# Wiegand_RF.net
KiCad netlist of a schematic drawn in EAGLE
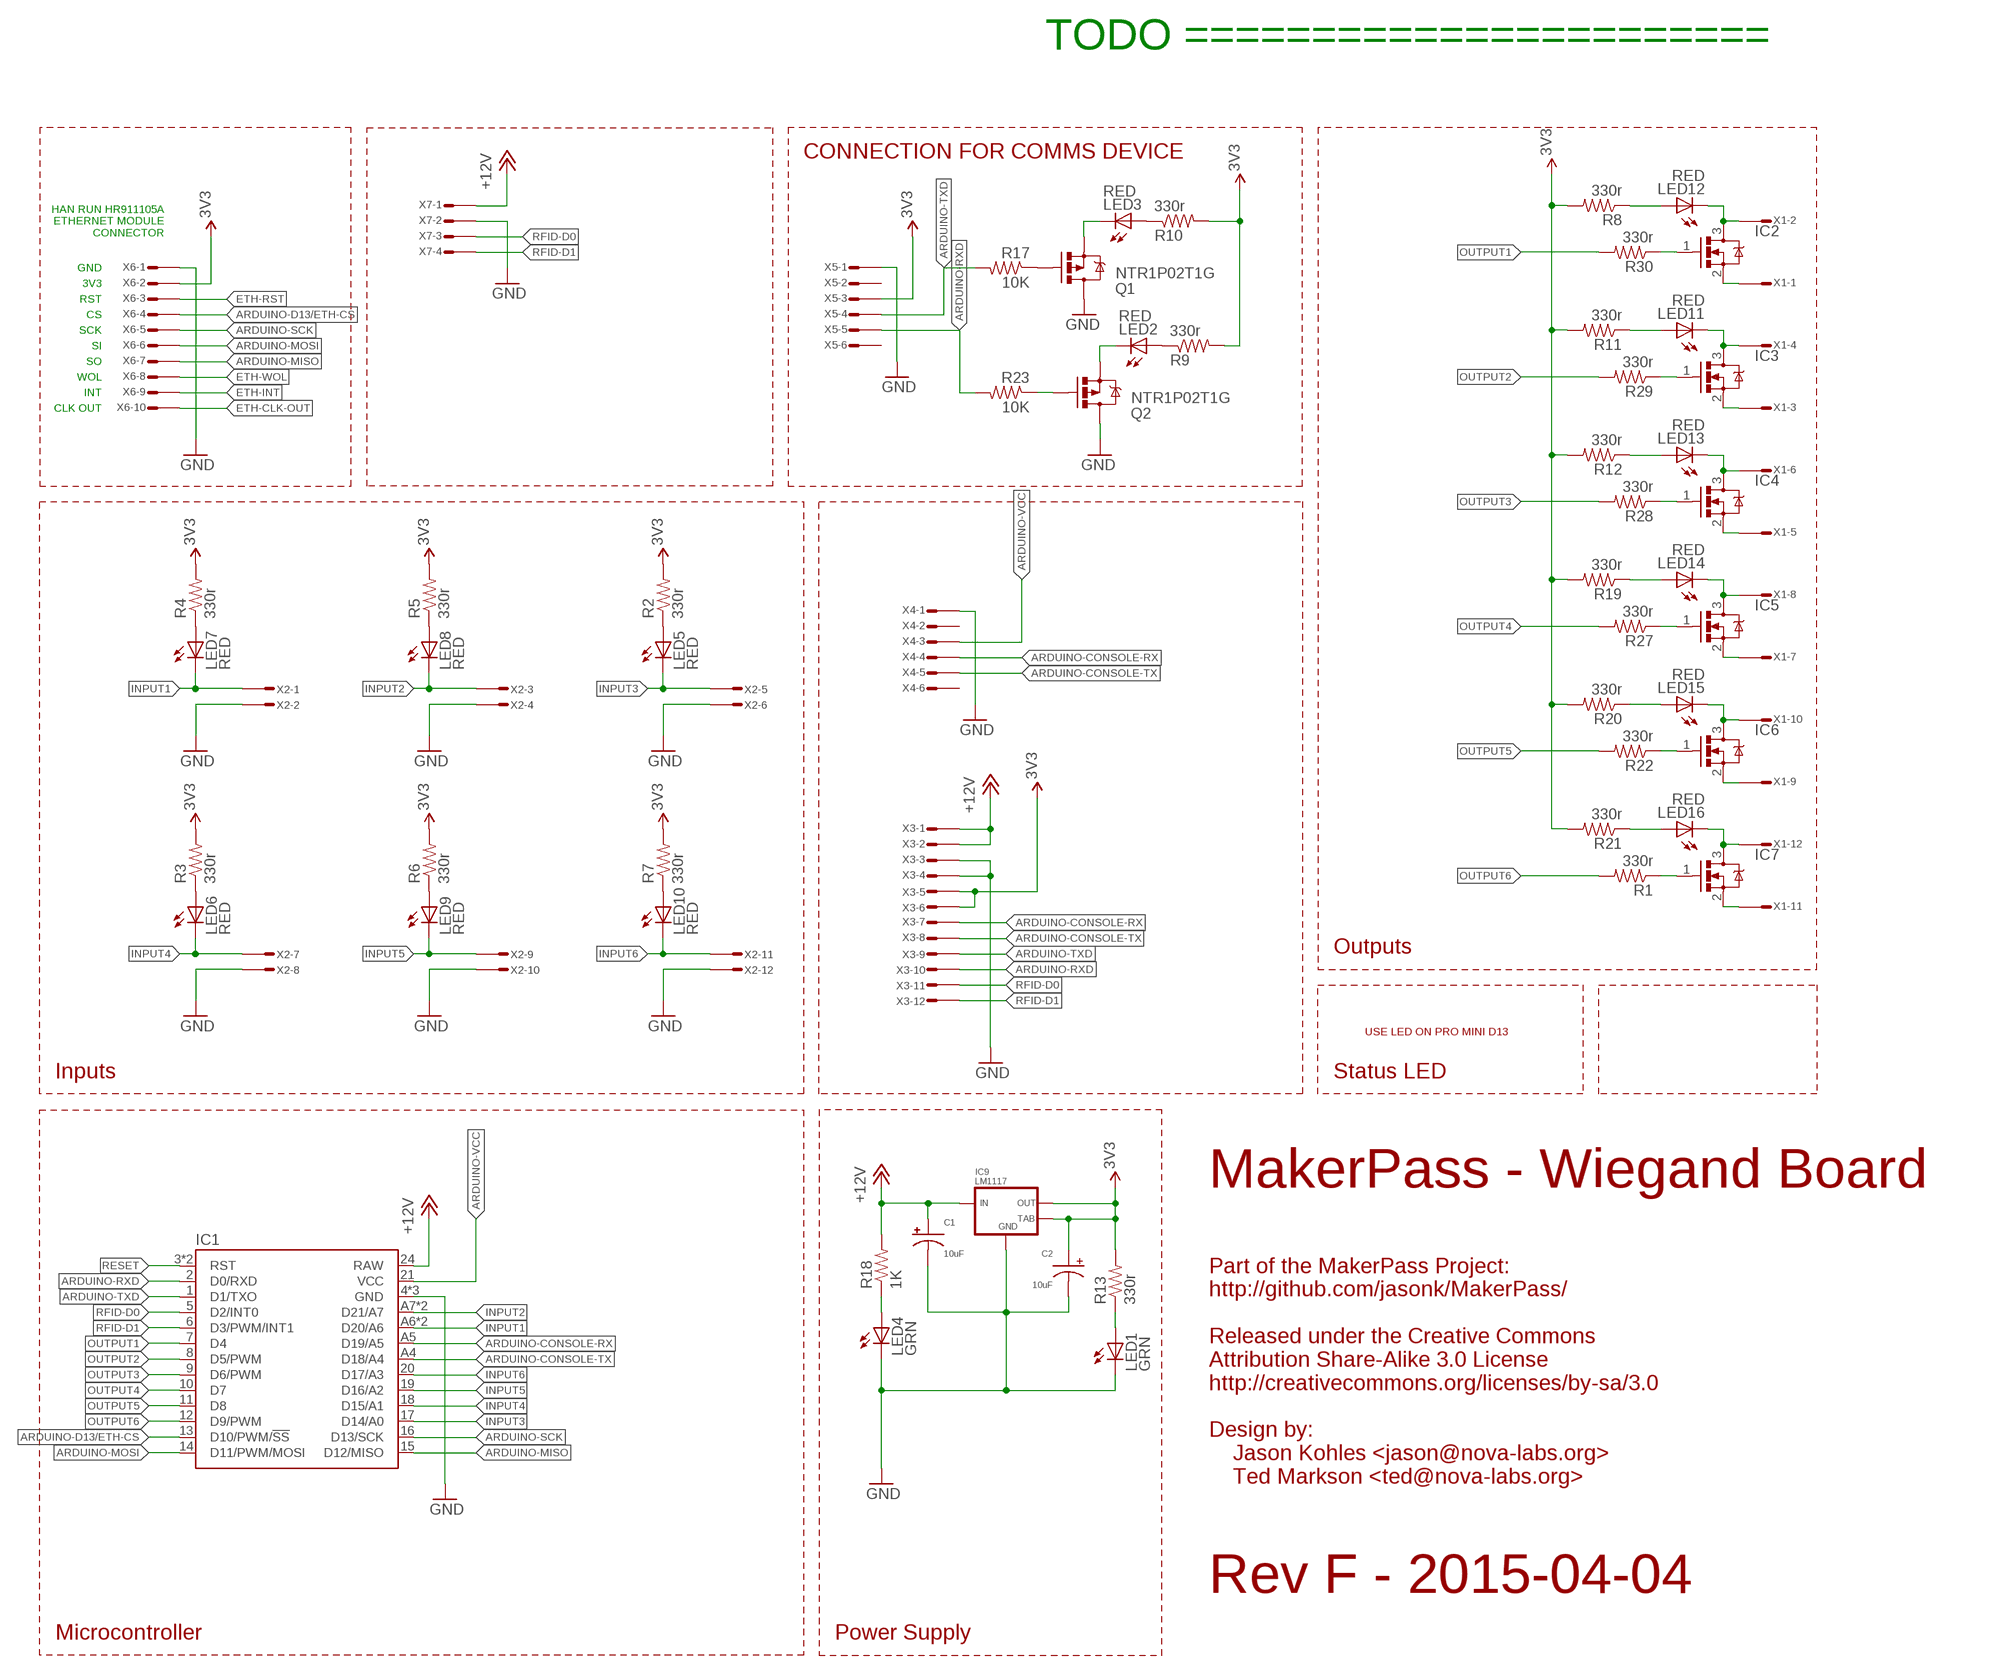
[diagram p0: schematic, sheet 1]

(export (version "E")
  (design (tool "Eeschema 10.0.6"))
  (components
    (comp (ref "C1")
      (value "10uF")
      (footprint "eagle-import:C-CAN-4.3")
      (fields
        (field (name "MFG") "UNITED CHEMI-CON")
        (field (name "MFG_PN") "EMVA250ADA100MD55G")
        (field (name "SUPP") "DIGIKEY")
        (field (name "SUPP_PN") "565-2100-1-ND")
      )
      (libsource (lib "eagle-import") (part "C-POL-CAN-4.3"))
    )
    (comp (ref "C2")
      (value "10uF")
      (footprint "eagle-import:C-CAN-4.3")
      (fields
        (field (name "MFG") "UNITED CHEMI-CON")
        (field (name "MFG_PN") "EMVA250ADA100MD55G")
        (field (name "SUPP") "DIGIKEY")
        (field (name "SUPP_PN") "565-2100-1-ND")
      )
      (libsource (lib "eagle-import") (part "C-POL-CAN-4.3"))
    )
    (comp (ref "IC1")
      (value "ARDUINO-PRO-MINI-ALIEXPRESS")
      (footprint "eagle-import:ARDUINO-PRO-MINI-ALIEXPRESS")
      (libsource (lib "eagle-import") (part "ARDUINO-PRO-MINI-ALIEXPRESS"))
    )
    (comp (ref "IC2")
      (value "MOSFET-NCHANNEL-SOT23")
      (footprint "eagle-import:SOT23")
      (fields (field (name "MFG") "DIODES INC"))
      (libsource (lib "eagle-import") (part "MOSFET-NCHANNEL-SOT23"))
    )
    (comp (ref "IC3")
      (value "MOSFET-NCHANNEL-SOT23")
      (footprint "eagle-import:SOT23")
      (fields (field (name "MFG") "DIODES INC"))
      (libsource (lib "eagle-import") (part "MOSFET-NCHANNEL-SOT23"))
    )
    (comp (ref "IC4")
      (value "MOSFET-NCHANNEL-SOT23")
      (footprint "eagle-import:SOT23")
      (fields (field (name "MFG") "DIODES INC"))
      (libsource (lib "eagle-import") (part "MOSFET-NCHANNEL-SOT23"))
    )
    (comp (ref "IC5")
      (value "MOSFET-NCHANNEL-SOT23")
      (footprint "eagle-import:SOT23")
      (fields (field (name "MFG") "DIODES INC"))
      (libsource (lib "eagle-import") (part "MOSFET-NCHANNEL-SOT23"))
    )
    (comp (ref "IC6")
      (value "MOSFET-NCHANNEL-SOT23")
      (footprint "eagle-import:SOT23")
      (fields (field (name "MFG") "DIODES INC"))
      (libsource (lib "eagle-import") (part "MOSFET-NCHANNEL-SOT23"))
    )
    (comp (ref "IC7")
      (value "MOSFET-NCHANNEL-SOT23")
      (footprint "eagle-import:SOT23")
      (fields (field (name "MFG") "DIODES INC"))
      (libsource (lib "eagle-import") (part "MOSFET-NCHANNEL-SOT23"))
    )
    (comp (ref "IC9")
      (value "LM1117")
      (footprint "eagle-import:SOT223")
      (fields
        (field (name "MFG") "TEXAS INSTRUMENTS")
        (field (name "MFG_PN") "LM1117MPX-3.3/NOPB")
        (field (name "SUPP") "DIGIKEY")
        (field (name "SUPP_PN") "LM1117MPX-3.3/NOPBCT-ND")
      )
      (libsource (lib "eagle-import") (part "VREG-LD1117-SOT223"))
    )
    (comp (ref "LED1")
      (value "GRN")
      (footprint "eagle-import:LED-805")
      (libsource (lib "eagle-import") (part "LED-0805"))
    )
    (comp (ref "LED2")
      (value "RED")
      (footprint "eagle-import:LED-805")
      (libsource (lib "eagle-import") (part "LED-0805"))
    )
    (comp (ref "LED3")
      (value "RED")
      (footprint "eagle-import:LED-805")
      (libsource (lib "eagle-import") (part "LED-0805"))
    )
    (comp (ref "LED4")
      (value "GRN")
      (footprint "eagle-import:LED-805")
      (libsource (lib "eagle-import") (part "LED-0805"))
    )
    (comp (ref "LED5")
      (value "RED")
      (footprint "eagle-import:LED-805")
      (libsource (lib "eagle-import") (part "LED-0805"))
    )
    (comp (ref "LED6")
      (value "RED")
      (footprint "eagle-import:LED-805")
      (libsource (lib "eagle-import") (part "LED-0805"))
    )
    (comp (ref "LED7")
      (value "RED")
      (footprint "eagle-import:LED-805")
      (libsource (lib "eagle-import") (part "LED-0805"))
    )
    (comp (ref "LED8")
      (value "RED")
      (footprint "eagle-import:LED-805")
      (libsource (lib "eagle-import") (part "LED-0805"))
    )
    (comp (ref "LED9")
      (value "RED")
      (footprint "eagle-import:LED-805")
      (libsource (lib "eagle-import") (part "LED-0805"))
    )
    (comp (ref "LED10")
      (value "RED")
      (footprint "eagle-import:LED-805")
      (libsource (lib "eagle-import") (part "LED-0805"))
    )
    (comp (ref "LED11")
      (value "RED")
      (footprint "eagle-import:LED-805")
      (libsource (lib "eagle-import") (part "LED-0805"))
    )
    (comp (ref "LED12")
      (value "RED")
      (footprint "eagle-import:LED-805")
      (libsource (lib "eagle-import") (part "LED-0805"))
    )
    (comp (ref "LED13")
      (value "RED")
      (footprint "eagle-import:LED-805")
      (libsource (lib "eagle-import") (part "LED-0805"))
    )
    (comp (ref "LED14")
      (value "RED")
      (footprint "eagle-import:LED-805")
      (libsource (lib "eagle-import") (part "LED-0805"))
    )
    (comp (ref "LED15")
      (value "RED")
      (footprint "eagle-import:LED-805")
      (libsource (lib "eagle-import") (part "LED-0805"))
    )
    (comp (ref "LED16")
      (value "RED")
      (footprint "eagle-import:LED-805")
      (libsource (lib "eagle-import") (part "LED-0805"))
    )
    (comp (ref "Q1")
      (value "NTR1P02T1G")
      (footprint "eagle-import:SOT23-3")
      (libsource (lib "eagle-import") (part "MOSFET-PCHANNELSMD"))
    )
    (comp (ref "Q2")
      (value "NTR1P02T1G")
      (footprint "eagle-import:SOT23-3")
      (libsource (lib "eagle-import") (part "MOSFET-PCHANNELSMD"))
    )
    (comp (ref "R1")
      (value "330r")
      (footprint "eagle-import:0603-RES")
      (libsource (lib "eagle-import") (part "RESISTOR0603-RES"))
    )
    (comp (ref "R2")
      (value "330r")
      (footprint "eagle-import:0603-RES")
      (libsource (lib "eagle-import") (part "RESISTOR0603-RES"))
    )
    (comp (ref "R3")
      (value "330r")
      (footprint "eagle-import:0603-RES")
      (libsource (lib "eagle-import") (part "RESISTOR0603-RES"))
    )
    (comp (ref "R4")
      (value "330r")
      (footprint "eagle-import:0603-RES")
      (libsource (lib "eagle-import") (part "RESISTOR0603-RES"))
    )
    (comp (ref "R5")
      (value "330r")
      (footprint "eagle-import:0603-RES")
      (libsource (lib "eagle-import") (part "RESISTOR0603-RES"))
    )
    (comp (ref "R6")
      (value "330r")
      (footprint "eagle-import:0603-RES")
      (libsource (lib "eagle-import") (part "RESISTOR0603-RES"))
    )
    (comp (ref "R7")
      (value "330r")
      (footprint "eagle-import:0603-RES")
      (libsource (lib "eagle-import") (part "RESISTOR0603-RES"))
    )
    (comp (ref "R8")
      (value "330r")
      (footprint "eagle-import:0603-RES")
      (libsource (lib "eagle-import") (part "RESISTOR0603-RES"))
    )
    (comp (ref "R9")
      (value "330r")
      (footprint "eagle-import:0603-RES")
      (libsource (lib "eagle-import") (part "RESISTOR0603-RES"))
    )
    (comp (ref "R10")
      (value "330r")
      (footprint "eagle-import:0603-RES")
      (libsource (lib "eagle-import") (part "RESISTOR0603-RES"))
    )
    (comp (ref "R11")
      (value "330r")
      (footprint "eagle-import:0603-RES")
      (libsource (lib "eagle-import") (part "RESISTOR0603-RES"))
    )
    (comp (ref "R12")
      (value "330r")
      (footprint "eagle-import:0603-RES")
      (libsource (lib "eagle-import") (part "RESISTOR0603-RES"))
    )
    (comp (ref "R13")
      (value "330r")
      (footprint "eagle-import:0603-RES")
      (libsource (lib "eagle-import") (part "RESISTOR0603-RES"))
    )
    (comp (ref "R17")
      (value "10K")
      (footprint "eagle-import:0603-RES")
      (libsource (lib "eagle-import") (part "RESISTOR0603-RES"))
    )
    (comp (ref "R18")
      (value "1K")
      (footprint "eagle-import:0603-RES")
      (libsource (lib "eagle-import") (part "RESISTOR0603-RES"))
    )
    (comp (ref "R19")
      (value "330r")
      (footprint "eagle-import:0603-RES")
      (libsource (lib "eagle-import") (part "RESISTOR0603-RES"))
    )
    (comp (ref "R20")
      (value "330r")
      (footprint "eagle-import:0603-RES")
      (libsource (lib "eagle-import") (part "RESISTOR0603-RES"))
    )
    (comp (ref "R21")
      (value "330r")
      (footprint "eagle-import:0603-RES")
      (libsource (lib "eagle-import") (part "RESISTOR0603-RES"))
    )
    (comp (ref "R22")
      (value "330r")
      (footprint "eagle-import:0603-RES")
      (libsource (lib "eagle-import") (part "RESISTOR0603-RES"))
    )
    (comp (ref "R23")
      (value "10K")
      (footprint "eagle-import:0603-RES")
      (libsource (lib "eagle-import") (part "RESISTOR0603-RES"))
    )
    (comp (ref "R27")
      (value "330r")
      (footprint "eagle-import:0603-RES")
      (libsource (lib "eagle-import") (part "RESISTOR0603-RES"))
    )
    (comp (ref "R28")
      (value "330r")
      (footprint "eagle-import:0603-RES")
      (libsource (lib "eagle-import") (part "RESISTOR0603-RES"))
    )
    (comp (ref "R29")
      (value "330r")
      (footprint "eagle-import:0603-RES")
      (libsource (lib "eagle-import") (part "RESISTOR0603-RES"))
    )
    (comp (ref "R30")
      (value "330r")
      (footprint "eagle-import:0603-RES")
      (libsource (lib "eagle-import") (part "RESISTOR0603-RES"))
    )
    (comp (ref "X1")
      (value "CON-1X12-TERMBLOCK-3.5MM")
      (footprint "eagle-import:CON-1X12-TERMBLOCK-3.5MM")
      (fields
        (field (name "MFG") "ON SHORE")
        (field (name "MFG_PN") "OSTTE120104")
        (field (name "SUPP") "DIGIKEY")
        (field (name "SUPP_PN") "ED2737-ND")
      )
      (libsource (lib "eagle-import") (part "CON-1X12-TERMBLOCK-3.5MM"))
    )
    (comp (ref "X2")
      (value "CON-1X12-TERMBLOCK-3.5MM")
      (footprint "eagle-import:CON-1X12-TERMBLOCK-3.5MM")
      (fields
        (field (name "MFG") "ON SHORE")
        (field (name "MFG_PN") "OSTTE120104")
        (field (name "SUPP") "DIGIKEY")
        (field (name "SUPP_PN") "ED2737-ND")
      )
      (libsource (lib "eagle-import") (part "CON-1X12-TERMBLOCK-3.5MM"))
    )
    (comp (ref "X3")
      (value "CON-1X12-TERMBLOCK-3.5MM")
      (footprint "eagle-import:CON-1X12-TERMBLOCK-3.5MM")
      (fields
        (field (name "MFG") "ON SHORE")
        (field (name "MFG_PN") "OSTTE120104")
        (field (name "SUPP") "DIGIKEY")
        (field (name "SUPP_PN") "ED2737-ND")
      )
      (libsource (lib "eagle-import") (part "CON-1X12-TERMBLOCK-3.5MM"))
    )
    (comp (ref "X4")
      (value "CON-1X6-FTDI-AVR")
      (footprint "eagle-import:CON-1X6-FTDI-AVR")
      (libsource (lib "eagle-import") (part "CON-1X6-FTDI-AVR"))
    )
    (comp (ref "X5")
      (value "CON-1X6-FTDI-AVR")
      (footprint "eagle-import:CON-1X6-FTDI-AVR")
      (libsource (lib "eagle-import") (part "CON-1X6-FTDI-AVR"))
    )
    (comp (ref "X6")
      (value "CON-2X5")
      (footprint "eagle-import:CON-2X5")
      (libsource (lib "eagle-import") (part "CON-2X5"))
    )
    (comp (ref "X7")
      (value "CON-1X4")
      (footprint "eagle-import:CON-1X4")
      (libsource (lib "eagle-import") (part "CON-1X4"))
    )
  )
  (nets
    (net (code "1") (name "+12V") (class "Default")
      (node (ref "C1") (pin "+") (pinfunction "+_+") (pintype "passive"))
      (node (ref "IC1") (pin "24") (pinfunction "RAW_24") (pintype "power_in"))
      (node (ref "IC9") (pin "IN") (pinfunction "IN_IN") (pintype "power_in"))
      (node (ref "R18") (pin "2") (pinfunction "2_2") (pintype "passive"))
      (node (ref "X3") (pin "1") (pinfunction "S_1") (pintype "passive"))
      (node (ref "X3") (pin "2") (pinfunction "S_2") (pintype "passive"))
      (node (ref "X7") (pin "1") (pinfunction "S_1") (pintype "passive"))
    )
    (net (code "2") (name "3V3") (class "Default")
      (node (ref "C2") (pin "+") (pinfunction "+_+") (pintype "passive"))
      (node (ref "IC9") (pin "OUT") (pinfunction "OUT_OUT") (pintype "power_in"))
      (node (ref "IC9") (pin "TAB") (pinfunction "TAB_TAB") (pintype "power_in"))
      (node (ref "R10") (pin "2") (pinfunction "2_2") (pintype "passive"))
      (node (ref "R11") (pin "2") (pinfunction "2_2") (pintype "passive"))
      (node (ref "R12") (pin "2") (pinfunction "2_2") (pintype "passive"))
      (node (ref "R13") (pin "2") (pinfunction "2_2") (pintype "passive"))
      (node (ref "R19") (pin "2") (pinfunction "2_2") (pintype "passive"))
      (node (ref "R2") (pin "2") (pinfunction "2_2") (pintype "passive"))
      (node (ref "R20") (pin "2") (pinfunction "2_2") (pintype "passive"))
      (node (ref "R21") (pin "2") (pinfunction "2_2") (pintype "passive"))
      (node (ref "R3") (pin "2") (pinfunction "2_2") (pintype "passive"))
      (node (ref "R4") (pin "2") (pinfunction "2_2") (pintype "passive"))
      (node (ref "R5") (pin "2") (pinfunction "2_2") (pintype "passive"))
      (node (ref "R6") (pin "2") (pinfunction "2_2") (pintype "passive"))
      (node (ref "R7") (pin "2") (pinfunction "2_2") (pintype "passive"))
      (node (ref "R8") (pin "2") (pinfunction "2_2") (pintype "passive"))
      (node (ref "R9") (pin "2") (pinfunction "2_2") (pintype "passive"))
      (node (ref "X3") (pin "5") (pinfunction "S_5") (pintype "passive"))
      (node (ref "X3") (pin "6") (pinfunction "S_6") (pintype "passive"))
      (node (ref "X5") (pin "3") (pinfunction "S_3") (pintype "passive"))
      (node (ref "X6") (pin "2") (pinfunction "S_2") (pintype "passive"))
    )
    (net (code "3") (name "ARDUINO-CONSOLE-RX") (class "Default")
      (node (ref "IC1") (pin "A5") (pinfunction "D19/A5_A5") (pintype "bidirectional"))
      (node (ref "X3") (pin "7") (pinfunction "S_7") (pintype "passive"))
      (node (ref "X4") (pin "4") (pinfunction "S_4") (pintype "passive"))
    )
    (net (code "4") (name "ARDUINO-CONSOLE-TX") (class "Default")
      (node (ref "IC1") (pin "A4") (pinfunction "D18/A4_A4") (pintype "bidirectional"))
      (node (ref "X3") (pin "8") (pinfunction "S_8") (pintype "passive"))
      (node (ref "X4") (pin "5") (pinfunction "S_5") (pintype "passive"))
    )
    (net (code "5") (name "ARDUINO-D13{slash}ETH-CS") (class "Default")
      (node (ref "IC1") (pin "13") (pinfunction "D10/PWM/~{SS}_13") (pintype "bidirectional"))
      (node (ref "X6") (pin "4") (pinfunction "S_4") (pintype "passive"))
    )
    (net (code "6") (name "ARDUINO-MISO") (class "Default")
      (node (ref "IC1") (pin "15") (pinfunction "D12/MISO_15") (pintype "bidirectional"))
      (node (ref "X6") (pin "7") (pinfunction "S_7") (pintype "passive"))
    )
    (net (code "7") (name "ARDUINO-MOSI") (class "Default")
      (node (ref "IC1") (pin "14") (pinfunction "D11/PWM/MOSI_14") (pintype "bidirectional"))
      (node (ref "X6") (pin "6") (pinfunction "S_6") (pintype "passive"))
    )
    (net (code "8") (name "ARDUINO-RXD") (class "Default")
      (node (ref "IC1") (pin "2") (pinfunction "D0/RXD_2") (pintype "bidirectional"))
      (node (ref "R23") (pin "2") (pinfunction "2_2") (pintype "passive"))
      (node (ref "X3") (pin "10") (pinfunction "S_10") (pintype "passive"))
      (node (ref "X5") (pin "5") (pinfunction "S_5") (pintype "passive"))
    )
    (net (code "9") (name "ARDUINO-SCK") (class "Default")
      (node (ref "IC1") (pin "16") (pinfunction "D13/SCK_16") (pintype "bidirectional"))
      (node (ref "X6") (pin "5") (pinfunction "S_5") (pintype "passive"))
    )
    (net (code "10") (name "ARDUINO-TXD") (class "Default")
      (node (ref "IC1") (pin "1") (pinfunction "D1/TXO_1") (pintype "bidirectional"))
      (node (ref "R17") (pin "2") (pinfunction "2_2") (pintype "passive"))
      (node (ref "X3") (pin "9") (pinfunction "S_9") (pintype "passive"))
      (node (ref "X5") (pin "4") (pinfunction "S_4") (pintype "passive"))
    )
    (net (code "11") (name "ARDUINO-VCC") (class "Default")
      (node (ref "IC1") (pin "21") (pinfunction "VCC_21") (pintype "power_in"))
      (node (ref "X4") (pin "3") (pinfunction "S_3") (pintype "passive"))
    )
    (net (code "12") (name "ETH-CLK-OUT") (class "Default")
      (node (ref "X6") (pin "10") (pinfunction "S_10") (pintype "passive"))
    )
    (net (code "13") (name "ETH-INT") (class "Default")
      (node (ref "X6") (pin "9") (pinfunction "S_9") (pintype "passive"))
    )
    (net (code "14") (name "ETH-RST") (class "Default")
      (node (ref "X6") (pin "3") (pinfunction "S_3") (pintype "passive"))
    )
    (net (code "15") (name "ETH-WOL") (class "Default")
      (node (ref "X6") (pin "8") (pinfunction "S_8") (pintype "passive"))
    )
    (net (code "16") (name "GND") (class "Default")
      (node (ref "C1") (pin "-") (pinfunction "-_-") (pintype "passive"))
      (node (ref "C2") (pin "-") (pinfunction "-_-") (pintype "passive"))
      (node (ref "IC1") (pin "23") (pinfunction "GND_23") (pintype "power_in"))
      (node (ref "IC1") (pin "25") (pinfunction "GND_25") (pintype "power_in"))
      (node (ref "IC1") (pin "4") (pinfunction "GND_4") (pintype "power_in"))
      (node (ref "IC9") (pin "GND") (pinfunction "GND_GND") (pintype "power_in"))
      (node (ref "LED1") (pin "C") (pinfunction "C_C") (pintype "passive"))
      (node (ref "LED4") (pin "C") (pinfunction "C_C") (pintype "passive"))
      (node (ref "Q1") (pin "3") (pinfunction "D_3") (pintype "passive"))
      (node (ref "Q2") (pin "3") (pinfunction "D_3") (pintype "passive"))
      (node (ref "X2") (pin "10") (pinfunction "S_10") (pintype "passive"))
      (node (ref "X2") (pin "12") (pinfunction "S_12") (pintype "passive"))
      (node (ref "X2") (pin "2") (pinfunction "S_2") (pintype "passive"))
      (node (ref "X2") (pin "4") (pinfunction "S_4") (pintype "passive"))
      (node (ref "X2") (pin "6") (pinfunction "S_6") (pintype "passive"))
      (node (ref "X2") (pin "8") (pinfunction "S_8") (pintype "passive"))
      (node (ref "X3") (pin "3") (pinfunction "S_3") (pintype "passive"))
      (node (ref "X3") (pin "4") (pinfunction "S_4") (pintype "passive"))
      (node (ref "X4") (pin "1") (pinfunction "S_1") (pintype "passive"))
      (node (ref "X5") (pin "1") (pinfunction "S_1") (pintype "passive"))
      (node (ref "X6") (pin "1") (pinfunction "S_1") (pintype "passive"))
      (node (ref "X7") (pin "2") (pinfunction "S_2") (pintype "passive"))
    )
    (net (code "17") (name "INPUT1") (class "Default")
      (node (ref "IC1") (pin "A6") (pinfunction "D20/A6_A6") (pintype "bidirectional"))
      (node (ref "IC1") (pin "A6@2") (pinfunction "D20/A6_A6@2") (pintype "bidirectional"))
      (node (ref "LED7") (pin "C") (pinfunction "C_C") (pintype "passive"))
      (node (ref "X2") (pin "1") (pinfunction "S_1") (pintype "passive"))
    )
    (net (code "18") (name "INPUT2") (class "Default")
      (node (ref "IC1") (pin "A7") (pinfunction "D21/A7_A7") (pintype "bidirectional"))
      (node (ref "IC1") (pin "A7@2") (pinfunction "D21/A7_A7@2") (pintype "bidirectional"))
      (node (ref "LED8") (pin "C") (pinfunction "C_C") (pintype "passive"))
      (node (ref "X2") (pin "3") (pinfunction "S_3") (pintype "passive"))
    )
    (net (code "19") (name "INPUT3") (class "Default")
      (node (ref "IC1") (pin "17") (pinfunction "D14/A0_17") (pintype "bidirectional"))
      (node (ref "LED5") (pin "C") (pinfunction "C_C") (pintype "passive"))
      (node (ref "X2") (pin "5") (pinfunction "S_5") (pintype "passive"))
    )
    (net (code "20") (name "INPUT4") (class "Default")
      (node (ref "IC1") (pin "18") (pinfunction "D15/A1_18") (pintype "bidirectional"))
      (node (ref "LED6") (pin "C") (pinfunction "C_C") (pintype "passive"))
      (node (ref "X2") (pin "7") (pinfunction "S_7") (pintype "passive"))
    )
    (net (code "21") (name "INPUT5") (class "Default")
      (node (ref "IC1") (pin "19") (pinfunction "D16/A2_19") (pintype "bidirectional"))
      (node (ref "LED9") (pin "C") (pinfunction "C_C") (pintype "passive"))
      (node (ref "X2") (pin "9") (pinfunction "S_9") (pintype "passive"))
    )
    (net (code "22") (name "INPUT6") (class "Default")
      (node (ref "IC1") (pin "20") (pinfunction "D17/A3_20") (pintype "bidirectional"))
      (node (ref "LED10") (pin "C") (pinfunction "C_C") (pintype "passive"))
      (node (ref "X2") (pin "11") (pinfunction "S_11") (pintype "passive"))
    )
    (net (code "23") (name "Net-(IC2-D)") (class "Default")
      (node (ref "IC2") (pin "3") (pinfunction "D_3") (pintype "passive"))
      (node (ref "LED12") (pin "C") (pinfunction "C_C") (pintype "passive"))
      (node (ref "X1") (pin "2") (pinfunction "S_2") (pintype "passive"))
    )
    (net (code "24") (name "Net-(IC2-G)") (class "Default")
      (node (ref "IC2") (pin "1") (pinfunction "G_1") (pintype "passive"))
      (node (ref "R30") (pin "1") (pinfunction "1_1") (pintype "passive"))
    )
    (net (code "25") (name "Net-(IC2-S)") (class "Default")
      (node (ref "IC2") (pin "2") (pinfunction "S_2") (pintype "passive"))
      (node (ref "X1") (pin "1") (pinfunction "S_1") (pintype "passive"))
    )
    (net (code "26") (name "Net-(IC3-D)") (class "Default")
      (node (ref "IC3") (pin "3") (pinfunction "D_3") (pintype "passive"))
      (node (ref "LED11") (pin "C") (pinfunction "C_C") (pintype "passive"))
      (node (ref "X1") (pin "4") (pinfunction "S_4") (pintype "passive"))
    )
    (net (code "27") (name "Net-(IC3-G)") (class "Default")
      (node (ref "IC3") (pin "1") (pinfunction "G_1") (pintype "passive"))
      (node (ref "R29") (pin "1") (pinfunction "1_1") (pintype "passive"))
    )
    (net (code "28") (name "Net-(IC3-S)") (class "Default")
      (node (ref "IC3") (pin "2") (pinfunction "S_2") (pintype "passive"))
      (node (ref "X1") (pin "3") (pinfunction "S_3") (pintype "passive"))
    )
    (net (code "29") (name "Net-(IC4-D)") (class "Default")
      (node (ref "IC4") (pin "3") (pinfunction "D_3") (pintype "passive"))
      (node (ref "LED13") (pin "C") (pinfunction "C_C") (pintype "passive"))
      (node (ref "X1") (pin "6") (pinfunction "S_6") (pintype "passive"))
    )
    (net (code "30") (name "Net-(IC4-G)") (class "Default")
      (node (ref "IC4") (pin "1") (pinfunction "G_1") (pintype "passive"))
      (node (ref "R28") (pin "1") (pinfunction "1_1") (pintype "passive"))
    )
    (net (code "31") (name "Net-(IC4-S)") (class "Default")
      (node (ref "IC4") (pin "2") (pinfunction "S_2") (pintype "passive"))
      (node (ref "X1") (pin "5") (pinfunction "S_5") (pintype "passive"))
    )
    (net (code "32") (name "Net-(IC5-D)") (class "Default")
      (node (ref "IC5") (pin "3") (pinfunction "D_3") (pintype "passive"))
      (node (ref "LED14") (pin "C") (pinfunction "C_C") (pintype "passive"))
      (node (ref "X1") (pin "8") (pinfunction "S_8") (pintype "passive"))
    )
    (net (code "33") (name "Net-(IC5-G)") (class "Default")
      (node (ref "IC5") (pin "1") (pinfunction "G_1") (pintype "passive"))
      (node (ref "R27") (pin "1") (pinfunction "1_1") (pintype "passive"))
    )
    (net (code "34") (name "Net-(IC5-S)") (class "Default")
      (node (ref "IC5") (pin "2") (pinfunction "S_2") (pintype "passive"))
      (node (ref "X1") (pin "7") (pinfunction "S_7") (pintype "passive"))
    )
    (net (code "35") (name "Net-(IC6-D)") (class "Default")
      (node (ref "IC6") (pin "3") (pinfunction "D_3") (pintype "passive"))
      (node (ref "LED15") (pin "C") (pinfunction "C_C") (pintype "passive"))
      (node (ref "X1") (pin "10") (pinfunction "S_10") (pintype "passive"))
    )
    (net (code "36") (name "Net-(IC6-G)") (class "Default")
      (node (ref "IC6") (pin "1") (pinfunction "G_1") (pintype "passive"))
      (node (ref "R22") (pin "1") (pinfunction "1_1") (pintype "passive"))
    )
    (net (code "37") (name "Net-(IC6-S)") (class "Default")
      (node (ref "IC6") (pin "2") (pinfunction "S_2") (pintype "passive"))
      (node (ref "X1") (pin "9") (pinfunction "S_9") (pintype "passive"))
    )
    (net (code "38") (name "Net-(IC7-D)") (class "Default")
      (node (ref "IC7") (pin "3") (pinfunction "D_3") (pintype "passive"))
      (node (ref "LED16") (pin "C") (pinfunction "C_C") (pintype "passive"))
      (node (ref "X1") (pin "12") (pinfunction "S_12") (pintype "passive"))
    )
    (net (code "39") (name "Net-(IC7-G)") (class "Default")
      (node (ref "IC7") (pin "1") (pinfunction "G_1") (pintype "passive"))
      (node (ref "R1") (pin "1") (pinfunction "1_1") (pintype "passive"))
    )
    (net (code "40") (name "Net-(IC7-S)") (class "Default")
      (node (ref "IC7") (pin "2") (pinfunction "S_2") (pintype "passive"))
      (node (ref "X1") (pin "11") (pinfunction "S_11") (pintype "passive"))
    )
    (net (code "41") (name "Net-(LED1-PadA)") (class "Default")
      (node (ref "LED1") (pin "A") (pinfunction "A_A") (pintype "passive"))
      (node (ref "R13") (pin "1") (pinfunction "1_1") (pintype "passive"))
    )
    (net (code "42") (name "Net-(LED2-PadA)") (class "Default")
      (node (ref "LED2") (pin "A") (pinfunction "A_A") (pintype "passive"))
      (node (ref "R9") (pin "1") (pinfunction "1_1") (pintype "passive"))
    )
    (net (code "43") (name "Net-(LED3-PadA)") (class "Default")
      (node (ref "LED3") (pin "A") (pinfunction "A_A") (pintype "passive"))
      (node (ref "R10") (pin "1") (pinfunction "1_1") (pintype "passive"))
    )
    (net (code "44") (name "Net-(LED4-PadA)") (class "Default")
      (node (ref "LED4") (pin "A") (pinfunction "A_A") (pintype "passive"))
      (node (ref "R18") (pin "1") (pinfunction "1_1") (pintype "passive"))
    )
    (net (code "45") (name "Net-(LED5-PadA)") (class "Default")
      (node (ref "LED5") (pin "A") (pinfunction "A_A") (pintype "passive"))
      (node (ref "R2") (pin "1") (pinfunction "1_1") (pintype "passive"))
    )
    (net (code "46") (name "Net-(LED6-PadA)") (class "Default")
      (node (ref "LED6") (pin "A") (pinfunction "A_A") (pintype "passive"))
      (node (ref "R3") (pin "1") (pinfunction "1_1") (pintype "passive"))
    )
    (net (code "47") (name "Net-(LED7-PadA)") (class "Default")
      (node (ref "LED7") (pin "A") (pinfunction "A_A") (pintype "passive"))
      (node (ref "R4") (pin "1") (pinfunction "1_1") (pintype "passive"))
    )
    (net (code "48") (name "Net-(LED8-PadA)") (class "Default")
      (node (ref "LED8") (pin "A") (pinfunction "A_A") (pintype "passive"))
      (node (ref "R5") (pin "1") (pinfunction "1_1") (pintype "passive"))
    )
    (net (code "49") (name "Net-(LED9-PadA)") (class "Default")
      (node (ref "LED9") (pin "A") (pinfunction "A_A") (pintype "passive"))
      (node (ref "R6") (pin "1") (pinfunction "1_1") (pintype "passive"))
    )
    (net (code "50") (name "Net-(LED10-PadA)") (class "Default")
      (node (ref "LED10") (pin "A") (pinfunction "A_A") (pintype "passive"))
      (node (ref "R7") (pin "1") (pinfunction "1_1") (pintype "passive"))
    )
    (net (code "51") (name "Net-(LED11-PadA)") (class "Default")
      (node (ref "LED11") (pin "A") (pinfunction "A_A") (pintype "passive"))
      (node (ref "R11") (pin "1") (pinfunction "1_1") (pintype "passive"))
    )
    (net (code "52") (name "Net-(LED12-PadA)") (class "Default")
      (node (ref "LED12") (pin "A") (pinfunction "A_A") (pintype "passive"))
      (node (ref "R8") (pin "1") (pinfunction "1_1") (pintype "passive"))
    )
    (net (code "53") (name "Net-(LED13-PadA)") (class "Default")
      (node (ref "LED13") (pin "A") (pinfunction "A_A") (pintype "passive"))
      (node (ref "R12") (pin "1") (pinfunction "1_1") (pintype "passive"))
    )
    (net (code "54") (name "Net-(LED14-PadA)") (class "Default")
      (node (ref "LED14") (pin "A") (pinfunction "A_A") (pintype "passive"))
      (node (ref "R19") (pin "1") (pinfunction "1_1") (pintype "passive"))
    )
    (net (code "55") (name "Net-(LED15-PadA)") (class "Default")
      (node (ref "LED15") (pin "A") (pinfunction "A_A") (pintype "passive"))
      (node (ref "R20") (pin "1") (pinfunction "1_1") (pintype "passive"))
    )
    (net (code "56") (name "Net-(LED16-PadA)") (class "Default")
      (node (ref "LED16") (pin "A") (pinfunction "A_A") (pintype "passive"))
      (node (ref "R21") (pin "1") (pinfunction "1_1") (pintype "passive"))
    )
    (net (code "57") (name "Net-(Q1-G)") (class "Default")
      (node (ref "Q1") (pin "1") (pinfunction "G_1") (pintype "passive"))
      (node (ref "R17") (pin "1") (pinfunction "1_1") (pintype "passive"))
    )
    (net (code "58") (name "Net-(Q1-S)") (class "Default")
      (node (ref "LED3") (pin "C") (pinfunction "C_C") (pintype "passive"))
      (node (ref "Q1") (pin "2") (pinfunction "S_2") (pintype "passive"))
    )
    (net (code "59") (name "Net-(Q2-G)") (class "Default")
      (node (ref "Q2") (pin "1") (pinfunction "G_1") (pintype "passive"))
      (node (ref "R23") (pin "1") (pinfunction "1_1") (pintype "passive"))
    )
    (net (code "60") (name "Net-(Q2-S)") (class "Default")
      (node (ref "LED2") (pin "C") (pinfunction "C_C") (pintype "passive"))
      (node (ref "Q2") (pin "2") (pinfunction "S_2") (pintype "passive"))
    )
    (net (code "61") (name "OUTPUT1") (class "Default")
      (node (ref "IC1") (pin "7") (pinfunction "D4_7") (pintype "bidirectional"))
      (node (ref "R30") (pin "2") (pinfunction "2_2") (pintype "passive"))
    )
    (net (code "62") (name "OUTPUT2") (class "Default")
      (node (ref "IC1") (pin "8") (pinfunction "D5/PWM_8") (pintype "bidirectional"))
      (node (ref "R29") (pin "2") (pinfunction "2_2") (pintype "passive"))
    )
    (net (code "63") (name "OUTPUT3") (class "Default")
      (node (ref "IC1") (pin "9") (pinfunction "D6/PWM_9") (pintype "bidirectional"))
      (node (ref "R28") (pin "2") (pinfunction "2_2") (pintype "passive"))
    )
    (net (code "64") (name "OUTPUT4") (class "Default")
      (node (ref "IC1") (pin "10") (pinfunction "D7_10") (pintype "bidirectional"))
      (node (ref "R27") (pin "2") (pinfunction "2_2") (pintype "passive"))
    )
    (net (code "65") (name "OUTPUT5") (class "Default")
      (node (ref "IC1") (pin "11") (pinfunction "D8_11") (pintype "bidirectional"))
      (node (ref "R22") (pin "2") (pinfunction "2_2") (pintype "passive"))
    )
    (net (code "66") (name "OUTPUT6") (class "Default")
      (node (ref "IC1") (pin "12") (pinfunction "D9/PWM_12") (pintype "bidirectional"))
      (node (ref "R1") (pin "2") (pinfunction "2_2") (pintype "passive"))
    )
    (net (code "67") (name "RESET") (class "Default")
      (node (ref "IC1") (pin "22") (pinfunction "RST_22") (pintype "input"))
      (node (ref "IC1") (pin "3") (pinfunction "RST_3") (pintype "input"))
    )
    (net (code "68") (name "RFID-D0") (class "Default")
      (node (ref "IC1") (pin "5") (pinfunction "D2/INT0_5") (pintype "bidirectional"))
      (node (ref "X3") (pin "11") (pinfunction "S_11") (pintype "passive"))
      (node (ref "X7") (pin "3") (pinfunction "S_3") (pintype "passive"))
    )
    (net (code "69") (name "RFID-D1") (class "Default")
      (node (ref "IC1") (pin "6") (pinfunction "D3/PWM/INT1_6") (pintype "bidirectional"))
      (node (ref "X3") (pin "12") (pinfunction "S_12") (pintype "passive"))
      (node (ref "X7") (pin "4") (pinfunction "S_4") (pintype "passive"))
    )
    (net (code "70") (name "unconnected-(X4B-S-Pad2)") (class "Default")
      (node (ref "X4") (pin "2") (pinfunction "S_2") (pintype "passive"))
    )
    (net (code "71") (name "unconnected-(X4F-S-Pad6)") (class "Default")
      (node (ref "X4") (pin "6") (pinfunction "S_6") (pintype "passive"))
    )
    (net (code "72") (name "unconnected-(X5B-S-Pad2)") (class "Default")
      (node (ref "X5") (pin "2") (pinfunction "S_2") (pintype "passive"))
    )
    (net (code "73") (name "unconnected-(X5F-S-Pad6)") (class "Default")
      (node (ref "X5") (pin "6") (pinfunction "S_6") (pintype "passive"))
    )
  )
)
